# 3-H.net
KiCad netlist of a schematic drawn in Altium Designer
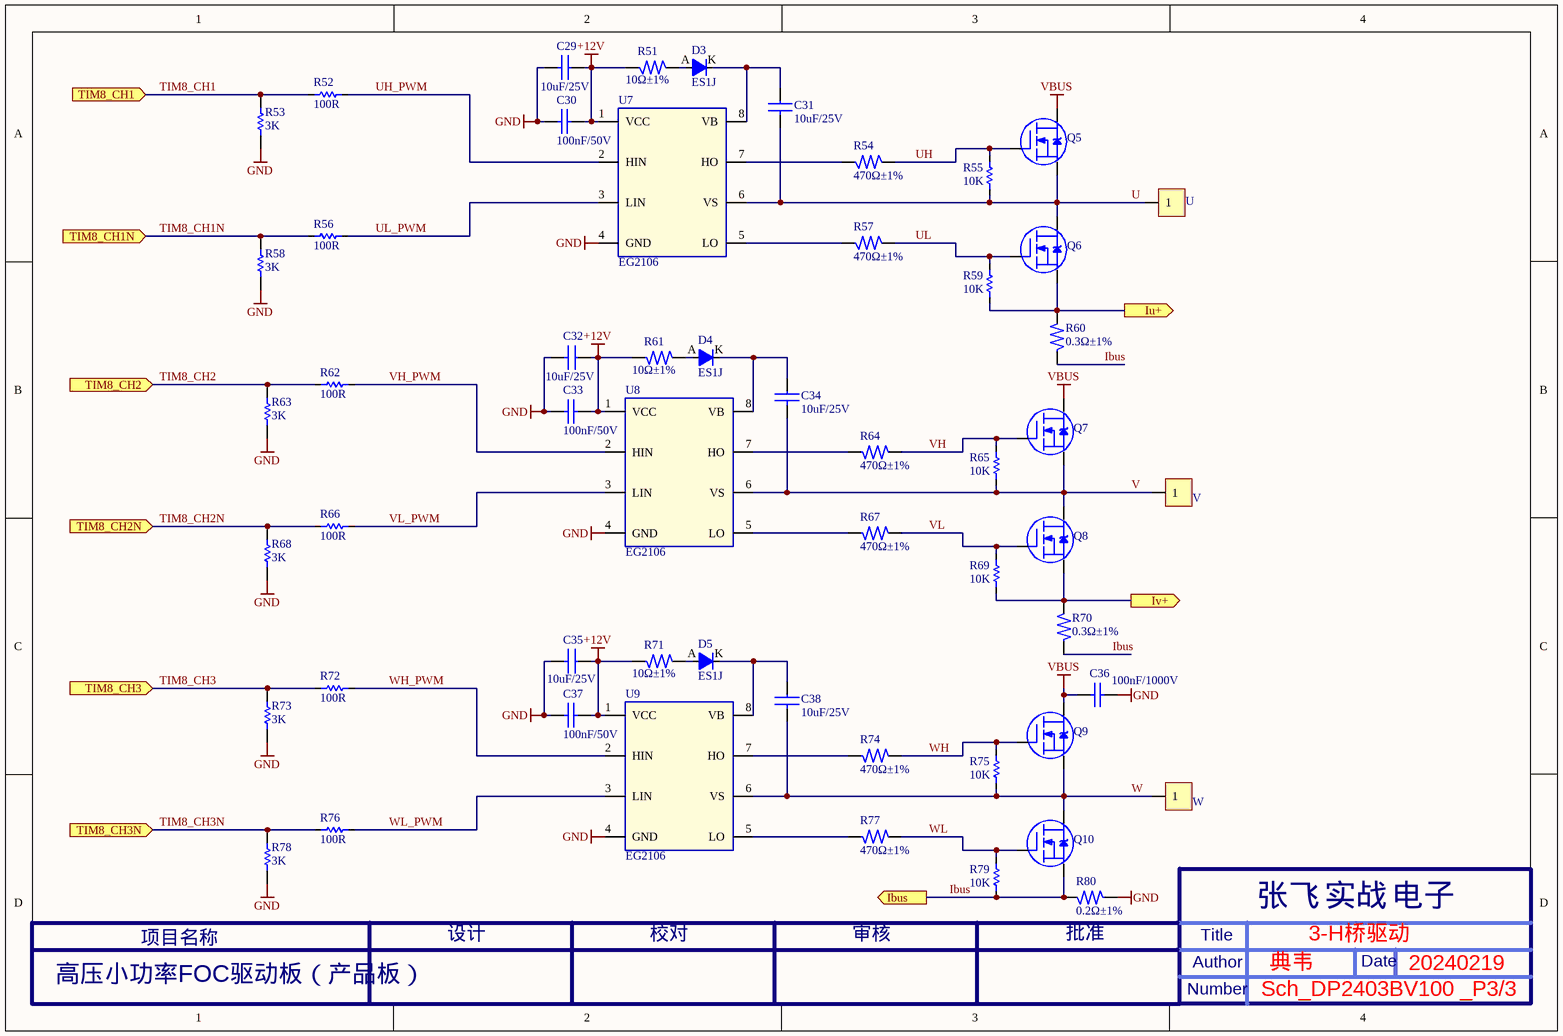
[diagram p0: 3-H桥驱动.SchDoc]

(export (version "E")
  (design (tool "Eeschema 10.0.6"))
  (components
    (comp (ref "C29")
      (value "10uF/25V")
      (footprint "C0805")
      (description "贴片电容")
      (fields
        (field (name "VOLTAGE") "<Voltage>")
        (field (name "MANUFACTURER") "TDK")
        (field (name "CREATED BY") "JJJ")
      )
      (libsource (lib "*") (part "CAP NP_0"))
    )
    (comp (ref "C30")
      (value "100nF/50V")
      (footprint "C0603")
      (description "贴片电容")
      (libsource (lib "*") (part "CAP"))
    )
    (comp (ref "C31")
      (value "10uF/25V")
      (footprint "C0805")
      (description "贴片电容")
      (fields
        (field (name "VOLTAGE") "<Voltage>")
        (field (name "MANUFACTURER") "TDK")
        (field (name "CREATED BY") "JJJ")
      )
      (libsource (lib "*") (part "CAP NP_0"))
    )
    (comp (ref "C32")
      (value "10uF/25V")
      (footprint "C0805")
      (description "贴片电容")
      (fields
        (field (name "VOLTAGE") "<Voltage>")
        (field (name "MANUFACTURER") "TDK")
        (field (name "CREATED BY") "JJJ")
      )
      (libsource (lib "*") (part "CAP NP_0"))
    )
    (comp (ref "C33")
      (value "100nF/50V")
      (footprint "C0603")
      (description "贴片电容")
      (libsource (lib "*") (part "CAP"))
    )
    (comp (ref "C34")
      (value "10uF/25V")
      (footprint "C0805")
      (description "贴片电容")
      (fields
        (field (name "VOLTAGE") "<Voltage>")
        (field (name "MANUFACTURER") "TDK")
        (field (name "CREATED BY") "JJJ")
      )
      (libsource (lib "*") (part "CAP NP_0"))
    )
    (comp (ref "C35")
      (value "10uF/25V")
      (footprint "C0805")
      (description "贴片电容")
      (fields
        (field (name "VOLTAGE") "<Voltage>")
        (field (name "MANUFACTURER") "TDK")
        (field (name "CREATED BY") "JJJ")
      )
      (libsource (lib "*") (part "CAP NP_0"))
    )
    (comp (ref "C36")
      (value "100nF/1000V")
      (footprint "C1812")
      (description "贴片电容")
      (libsource (lib "*") (part "CAP"))
    )
    (comp (ref "C37")
      (value "100nF/50V")
      (footprint "C0603")
      (description "贴片电容")
      (libsource (lib "*") (part "CAP"))
    )
    (comp (ref "C38")
      (value "10uF/25V")
      (footprint "C0805")
      (description "贴片电容")
      (fields
        (field (name "VOLTAGE") "<Voltage>")
        (field (name "MANUFACTURER") "TDK")
        (field (name "CREATED BY") "JJJ")
      )
      (libsource (lib "*") (part "CAP NP_0"))
    )
    (comp (ref "D3")
      (value "ES1J")
      (footprint "DO-214AC(SMA)")
      (description "二极管")
      (libsource (lib "ZF-V1.00(2022-6-13)") (part "DIO"))
    )
    (comp (ref "D4")
      (value "ES1J")
      (footprint "DO-214AC(SMA)")
      (description "二极管")
      (libsource (lib "ZF-V1.00(2022-6-13)") (part "DIO"))
    )
    (comp (ref "D5")
      (value "ES1J")
      (footprint "DO-214AC(SMA)")
      (description "二极管")
      (libsource (lib "ZF-V1.00(2022-6-13)") (part "DIO"))
    )
    (comp (ref "Q5")
      (value "MOT5N50D")
      (footprint "TO-252AA")
      (libsource (lib "吹风机-20231226") (part "MOT5N50D"))
    )
    (comp (ref "Q6")
      (value "MOT5N50D")
      (footprint "TO-252AA")
      (libsource (lib "吹风机-20231226") (part "MOT5N50D"))
    )
    (comp (ref "Q7")
      (value "MOT5N50D")
      (footprint "TO-252AA")
      (libsource (lib "吹风机-20231226") (part "MOT5N50D"))
    )
    (comp (ref "Q8")
      (value "MOT5N50D")
      (footprint "TO-252AA")
      (libsource (lib "吹风机-20231226") (part "MOT5N50D"))
    )
    (comp (ref "Q9")
      (value "MOT5N50D")
      (footprint "TO-252AA")
      (libsource (lib "吹风机-20231226") (part "MOT5N50D"))
    )
    (comp (ref "Q10")
      (value "MOT5N50D")
      (footprint "TO-252AA")
      (libsource (lib "吹风机-20231226") (part "MOT5N50D"))
    )
    (comp (ref "R51") (value "10Ω±1%") (footprint "R0805") (libsource (lib "EV") (part "RES")))
    (comp (ref "R52")
      (value "100R")
      (footprint "R0603")
      (description "电阻")
      (fields
        (field (name "MANUFACTURER") "Generic Components")
        (field (name "PUBLISHER") "Altium Hobart Technology Centre")
      )
      (libsource (lib "ZF-V1.00(2022-6-13)") (part "Res"))
    )
    (comp (ref "R53")
      (value "3K")
      (footprint "R0603")
      (description "电阻")
      (fields
        (field (name "MANUFACTURER") "Generic Components")
        (field (name "PUBLISHER") "Altium Hobart Technology Centre")
      )
      (libsource (lib "ZF_SchLib_V0.15") (part "Res"))
    )
    (comp (ref "R54") (value "470Ω±1%") (footprint "R0603") (libsource (lib "EV") (part "RES")))
    (comp (ref "R55")
      (value "10K")
      (footprint "R0603")
      (description "电阻")
      (fields
        (field (name "MANUFACTURER") "Generic Components")
        (field (name "PUBLISHER") "Altium Hobart Technology Centre")
      )
      (libsource (lib "ZF-V1.00(2022-6-13)") (part "Res"))
    )
    (comp (ref "R56")
      (value "100R")
      (footprint "R0603")
      (description "电阻")
      (fields
        (field (name "MANUFACTURER") "Generic Components")
        (field (name "PUBLISHER") "Altium Hobart Technology Centre")
      )
      (libsource (lib "ZF-V1.00(2022-6-13)") (part "Res"))
    )
    (comp (ref "R57") (value "470Ω±1%") (footprint "R0603") (libsource (lib "EV") (part "RES")))
    (comp (ref "R58")
      (value "3K")
      (footprint "R0603")
      (description "电阻")
      (fields
        (field (name "MANUFACTURER") "Generic Components")
        (field (name "PUBLISHER") "Altium Hobart Technology Centre")
      )
      (libsource (lib "ZF_SchLib_V0.15") (part "Res"))
    )
    (comp (ref "R59")
      (value "10K")
      (footprint "R0603")
      (description "电阻")
      (fields
        (field (name "MANUFACTURER") "Generic Components")
        (field (name "PUBLISHER") "Altium Hobart Technology Centre")
      )
      (libsource (lib "ZF-V1.00(2022-6-13)") (part "Res"))
    )
    (comp (ref "R60") (value "0.3Ω±1%") (footprint "R1206") (libsource (lib "EV") (part "RES")))
    (comp (ref "R61") (value "10Ω±1%") (footprint "R0805") (libsource (lib "EV") (part "RES")))
    (comp (ref "R62")
      (value "100R")
      (footprint "R0603")
      (description "电阻")
      (fields
        (field (name "MANUFACTURER") "Generic Components")
        (field (name "PUBLISHER") "Altium Hobart Technology Centre")
      )
      (libsource (lib "ZF-V1.00(2022-6-13)") (part "Res"))
    )
    (comp (ref "R63")
      (value "3K")
      (footprint "R0603")
      (description "电阻")
      (fields
        (field (name "MANUFACTURER") "Generic Components")
        (field (name "PUBLISHER") "Altium Hobart Technology Centre")
      )
      (libsource (lib "ZF_SchLib_V0.15") (part "Res"))
    )
    (comp (ref "R64") (value "470Ω±1%") (footprint "R0603") (libsource (lib "EV") (part "RES")))
    (comp (ref "R65")
      (value "10K")
      (footprint "R0603")
      (description "电阻")
      (fields
        (field (name "MANUFACTURER") "Generic Components")
        (field (name "PUBLISHER") "Altium Hobart Technology Centre")
      )
      (libsource (lib "ZF-V1.00(2022-6-13)") (part "Res"))
    )
    (comp (ref "R66")
      (value "100R")
      (footprint "R0603")
      (description "电阻")
      (fields
        (field (name "MANUFACTURER") "Generic Components")
        (field (name "PUBLISHER") "Altium Hobart Technology Centre")
      )
      (libsource (lib "ZF-V1.00(2022-6-13)") (part "Res"))
    )
    (comp (ref "R67") (value "470Ω±1%") (footprint "R0603") (libsource (lib "EV") (part "RES")))
    (comp (ref "R68")
      (value "3K")
      (footprint "R0603")
      (description "电阻")
      (fields
        (field (name "MANUFACTURER") "Generic Components")
        (field (name "PUBLISHER") "Altium Hobart Technology Centre")
      )
      (libsource (lib "ZF_SchLib_V0.15") (part "Res"))
    )
    (comp (ref "R69")
      (value "10K")
      (footprint "R0603")
      (description "电阻")
      (fields
        (field (name "MANUFACTURER") "Generic Components")
        (field (name "PUBLISHER") "Altium Hobart Technology Centre")
      )
      (libsource (lib "ZF-V1.00(2022-6-13)") (part "Res"))
    )
    (comp (ref "R70") (value "0.3Ω±1%") (footprint "R1206") (libsource (lib "EV") (part "RES")))
    (comp (ref "R71") (value "10Ω±1%") (footprint "R0805") (libsource (lib "EV") (part "RES")))
    (comp (ref "R72")
      (value "100R")
      (footprint "R0603")
      (description "电阻")
      (fields
        (field (name "MANUFACTURER") "Generic Components")
        (field (name "PUBLISHER") "Altium Hobart Technology Centre")
      )
      (libsource (lib "ZF-V1.00(2022-6-13)") (part "Res"))
    )
    (comp (ref "R73")
      (value "3K")
      (footprint "R0603")
      (description "电阻")
      (fields
        (field (name "MANUFACTURER") "Generic Components")
        (field (name "PUBLISHER") "Altium Hobart Technology Centre")
      )
      (libsource (lib "ZF_SchLib_V0.15") (part "Res"))
    )
    (comp (ref "R74") (value "470Ω±1%") (footprint "R0603") (libsource (lib "EV") (part "RES")))
    (comp (ref "R75")
      (value "10K")
      (footprint "R0603")
      (description "电阻")
      (fields
        (field (name "MANUFACTURER") "Generic Components")
        (field (name "PUBLISHER") "Altium Hobart Technology Centre")
      )
      (libsource (lib "ZF-V1.00(2022-6-13)") (part "Res"))
    )
    (comp (ref "R76")
      (value "100R")
      (footprint "R0603")
      (description "电阻")
      (fields
        (field (name "MANUFACTURER") "Generic Components")
        (field (name "PUBLISHER") "Altium Hobart Technology Centre")
      )
      (libsource (lib "ZF-V1.00(2022-6-13)") (part "Res"))
    )
    (comp (ref "R77") (value "470Ω±1%") (footprint "R0603") (libsource (lib "EV") (part "RES")))
    (comp (ref "R78")
      (value "3K")
      (footprint "R0603")
      (description "电阻")
      (fields
        (field (name "MANUFACTURER") "Generic Components")
        (field (name "PUBLISHER") "Altium Hobart Technology Centre")
      )
      (libsource (lib "ZF_SchLib_V0.15") (part "Res"))
    )
    (comp (ref "R79")
      (value "10K")
      (footprint "R0603")
      (description "电阻")
      (fields
        (field (name "MANUFACTURER") "Generic Components")
        (field (name "PUBLISHER") "Altium Hobart Technology Centre")
      )
      (libsource (lib "ZF-V1.00(2022-6-13)") (part "Res"))
    )
    (comp (ref "R80") (value "0.2Ω±1%") (footprint "R1206") (libsource (lib "EV") (part "RES")))
    (comp (ref "U")
      (value "U")
      (footprint "IGBT-PIN")
      (description "1Pin")
      (libsource (lib "ZF-V1.00(2022-6-13)") (part "Pin1"))
    )
    (comp (ref "U7") (value "EG2106") (footprint "SOIC-8") (libsource (lib "吹风机") (part "EG2106")))
    (comp (ref "U8") (value "EG2106") (footprint "SOIC-8") (libsource (lib "吹风机") (part "EG2106")))
    (comp (ref "U9") (value "EG2106") (footprint "SOIC-8") (libsource (lib "吹风机") (part "EG2106")))
    (comp (ref "V")
      (value "V")
      (footprint "IGBT-PIN")
      (description "1Pin")
      (libsource (lib "ZF-V1.00(2022-6-13)") (part "Pin1"))
    )
    (comp (ref "W")
      (value "W")
      (footprint "IGBT-PIN")
      (description "1Pin")
      (libsource (lib "ZF-V1.00(2022-6-13)") (part "Pin1"))
    )
  )
  (nets
    (net (code "1") (name "+12V") (class "Default")
      (node (ref "C29") (pin "1") (pinfunction "1_1") (pintype "passive"))
      (node (ref "C30") (pin "2") (pinfunction "2_2") (pintype "passive"))
      (node (ref "C32") (pin "1") (pinfunction "1_1") (pintype "passive"))
      (node (ref "C33") (pin "2") (pinfunction "2_2") (pintype "passive"))
      (node (ref "C35") (pin "1") (pinfunction "1_1") (pintype "passive"))
      (node (ref "C37") (pin "2") (pinfunction "2_2") (pintype "passive"))
      (node (ref "R51") (pin "1") (pintype "passive"))
      (node (ref "R61") (pin "1") (pintype "passive"))
      (node (ref "R71") (pin "1") (pintype "passive"))
      (node (ref "U7") (pin "1") (pinfunction "VCC_1") (pintype "passive"))
      (node (ref "U8") (pin "1") (pinfunction "VCC_1") (pintype "passive"))
      (node (ref "U9") (pin "1") (pinfunction "VCC_1") (pintype "passive"))
    )
    (net (code "2") (name "/Ibus") (class "Default")
      (node (ref "Q10") (pin "S") (pinfunction "S_S") (pintype "passive"))
      (node (ref "R60") (pin "1") (pintype "passive"))
      (node (ref "R70") (pin "1") (pintype "passive"))
      (node (ref "R79") (pin "2") (pinfunction "2_2") (pintype "passive"))
      (node (ref "R80") (pin "2") (pintype "passive"))
    )
    (net (code "3") (name "/Iu+") (class "Default")
      (node (ref "Q6") (pin "S") (pinfunction "S_S") (pintype "passive"))
      (node (ref "R59") (pin "2") (pinfunction "2_2") (pintype "passive"))
      (node (ref "R60") (pin "2") (pintype "passive"))
    )
    (net (code "4") (name "/Iv+") (class "Default")
      (node (ref "Q8") (pin "S") (pinfunction "S_S") (pintype "passive"))
      (node (ref "R69") (pin "2") (pinfunction "2_2") (pintype "passive"))
      (node (ref "R70") (pin "2") (pintype "passive"))
    )
    (net (code "5") (name "/TIM8_CH1") (class "Default")
      (node (ref "R52") (pin "1") (pinfunction "1_1") (pintype "passive"))
      (node (ref "R53") (pin "1") (pinfunction "1_1") (pintype "passive"))
    )
    (net (code "6") (name "/TIM8_CH1N") (class "Default")
      (node (ref "R56") (pin "1") (pinfunction "1_1") (pintype "passive"))
      (node (ref "R58") (pin "1") (pinfunction "1_1") (pintype "passive"))
    )
    (net (code "7") (name "/TIM8_CH2") (class "Default")
      (node (ref "R62") (pin "1") (pinfunction "1_1") (pintype "passive"))
      (node (ref "R63") (pin "1") (pinfunction "1_1") (pintype "passive"))
    )
    (net (code "8") (name "/TIM8_CH2N") (class "Default")
      (node (ref "R66") (pin "1") (pinfunction "1_1") (pintype "passive"))
      (node (ref "R68") (pin "1") (pinfunction "1_1") (pintype "passive"))
    )
    (net (code "9") (name "/TIM8_CH3") (class "Default")
      (node (ref "R72") (pin "1") (pinfunction "1_1") (pintype "passive"))
      (node (ref "R73") (pin "1") (pinfunction "1_1") (pintype "passive"))
    )
    (net (code "10") (name "/TIM8_CH3N") (class "Default")
      (node (ref "R76") (pin "1") (pinfunction "1_1") (pintype "passive"))
      (node (ref "R78") (pin "1") (pinfunction "1_1") (pintype "passive"))
    )
    (net (code "11") (name "/U") (class "Default")
      (node (ref "C31") (pin "2") (pinfunction "2_2") (pintype "passive"))
      (node (ref "Q5") (pin "S") (pinfunction "S_S") (pintype "passive"))
      (node (ref "Q6") (pin "D") (pinfunction "D_D") (pintype "passive"))
      (node (ref "R55") (pin "2") (pinfunction "2_2") (pintype "passive"))
      (node (ref "U") (pin "1") (pinfunction "1_1") (pintype "passive"))
      (node (ref "U7") (pin "6") (pinfunction "VS_6") (pintype "passive"))
    )
    (net (code "12") (name "/UH") (class "Default")
      (node (ref "Q5") (pin "G") (pinfunction "G_G") (pintype "passive"))
      (node (ref "R54") (pin "2") (pintype "passive"))
      (node (ref "R55") (pin "1") (pinfunction "1_1") (pintype "passive"))
    )
    (net (code "13") (name "/UH_PWM") (class "Default")
      (node (ref "R52") (pin "2") (pinfunction "2_2") (pintype "passive"))
      (node (ref "U7") (pin "2") (pinfunction "HIN_2") (pintype "passive"))
    )
    (net (code "14") (name "/UL") (class "Default")
      (node (ref "Q6") (pin "G") (pinfunction "G_G") (pintype "passive"))
      (node (ref "R57") (pin "2") (pintype "passive"))
      (node (ref "R59") (pin "1") (pinfunction "1_1") (pintype "passive"))
    )
    (net (code "15") (name "/UL_PWM") (class "Default")
      (node (ref "R56") (pin "2") (pinfunction "2_2") (pintype "passive"))
      (node (ref "U7") (pin "3") (pinfunction "LIN_3") (pintype "passive"))
    )
    (net (code "16") (name "/V") (class "Default")
      (node (ref "C34") (pin "2") (pinfunction "2_2") (pintype "passive"))
      (node (ref "Q7") (pin "S") (pinfunction "S_S") (pintype "passive"))
      (node (ref "Q8") (pin "D") (pinfunction "D_D") (pintype "passive"))
      (node (ref "R65") (pin "2") (pinfunction "2_2") (pintype "passive"))
      (node (ref "U8") (pin "6") (pinfunction "VS_6") (pintype "passive"))
      (node (ref "V") (pin "1") (pinfunction "1_1") (pintype "passive"))
    )
    (net (code "17") (name "/VH") (class "Default")
      (node (ref "Q7") (pin "G") (pinfunction "G_G") (pintype "passive"))
      (node (ref "R64") (pin "2") (pintype "passive"))
      (node (ref "R65") (pin "1") (pinfunction "1_1") (pintype "passive"))
    )
    (net (code "18") (name "/VH_PWM") (class "Default")
      (node (ref "R62") (pin "2") (pinfunction "2_2") (pintype "passive"))
      (node (ref "U8") (pin "2") (pinfunction "HIN_2") (pintype "passive"))
    )
    (net (code "19") (name "/VL") (class "Default")
      (node (ref "Q8") (pin "G") (pinfunction "G_G") (pintype "passive"))
      (node (ref "R67") (pin "2") (pintype "passive"))
      (node (ref "R69") (pin "1") (pinfunction "1_1") (pintype "passive"))
    )
    (net (code "20") (name "/VL_PWM") (class "Default")
      (node (ref "R66") (pin "2") (pinfunction "2_2") (pintype "passive"))
      (node (ref "U8") (pin "3") (pinfunction "LIN_3") (pintype "passive"))
    )
    (net (code "21") (name "/W") (class "Default")
      (node (ref "C38") (pin "2") (pinfunction "2_2") (pintype "passive"))
      (node (ref "Q10") (pin "D") (pinfunction "D_D") (pintype "passive"))
      (node (ref "Q9") (pin "S") (pinfunction "S_S") (pintype "passive"))
      (node (ref "R75") (pin "2") (pinfunction "2_2") (pintype "passive"))
      (node (ref "U9") (pin "6") (pinfunction "VS_6") (pintype "passive"))
      (node (ref "W") (pin "1") (pinfunction "1_1") (pintype "passive"))
    )
    (net (code "22") (name "/WH") (class "Default")
      (node (ref "Q9") (pin "G") (pinfunction "G_G") (pintype "passive"))
      (node (ref "R74") (pin "2") (pintype "passive"))
      (node (ref "R75") (pin "1") (pinfunction "1_1") (pintype "passive"))
    )
    (net (code "23") (name "/WH_PWM") (class "Default")
      (node (ref "R72") (pin "2") (pinfunction "2_2") (pintype "passive"))
      (node (ref "U9") (pin "2") (pinfunction "HIN_2") (pintype "passive"))
    )
    (net (code "24") (name "/WL") (class "Default")
      (node (ref "Q10") (pin "G") (pinfunction "G_G") (pintype "passive"))
      (node (ref "R77") (pin "2") (pintype "passive"))
      (node (ref "R79") (pin "1") (pinfunction "1_1") (pintype "passive"))
    )
    (net (code "25") (name "/WL_PWM") (class "Default")
      (node (ref "R76") (pin "2") (pinfunction "2_2") (pintype "passive"))
      (node (ref "U9") (pin "3") (pinfunction "LIN_3") (pintype "passive"))
    )
    (net (code "26") (name "GND") (class "Default")
      (node (ref "C29") (pin "2") (pinfunction "2_2") (pintype "passive"))
      (node (ref "C30") (pin "1") (pinfunction "1_1") (pintype "passive"))
      (node (ref "C32") (pin "2") (pinfunction "2_2") (pintype "passive"))
      (node (ref "C33") (pin "1") (pinfunction "1_1") (pintype "passive"))
      (node (ref "C35") (pin "2") (pinfunction "2_2") (pintype "passive"))
      (node (ref "C36") (pin "2") (pinfunction "2_2") (pintype "passive"))
      (node (ref "C37") (pin "1") (pinfunction "1_1") (pintype "passive"))
      (node (ref "R53") (pin "2") (pinfunction "2_2") (pintype "passive"))
      (node (ref "R58") (pin "2") (pinfunction "2_2") (pintype "passive"))
      (node (ref "R63") (pin "2") (pinfunction "2_2") (pintype "passive"))
      (node (ref "R68") (pin "2") (pinfunction "2_2") (pintype "passive"))
      (node (ref "R73") (pin "2") (pinfunction "2_2") (pintype "passive"))
      (node (ref "R78") (pin "2") (pinfunction "2_2") (pintype "passive"))
      (node (ref "R80") (pin "1") (pintype "passive"))
      (node (ref "U7") (pin "4") (pinfunction "GND_4") (pintype "passive"))
      (node (ref "U8") (pin "4") (pinfunction "GND_4") (pintype "passive"))
      (node (ref "U9") (pin "4") (pinfunction "GND_4") (pintype "passive"))
    )
    (net (code "27") (name "Net-(D3-PadA)") (class "Default")
      (node (ref "D3") (pin "A") (pinfunction "A_A") (pintype "passive"))
      (node (ref "R51") (pin "2") (pintype "passive"))
    )
    (net (code "28") (name "Net-(D4-PadA)") (class "Default")
      (node (ref "D4") (pin "A") (pinfunction "A_A") (pintype "passive"))
      (node (ref "R61") (pin "2") (pintype "passive"))
    )
    (net (code "29") (name "Net-(D5-PadA)") (class "Default")
      (node (ref "D5") (pin "A") (pinfunction "A_A") (pintype "passive"))
      (node (ref "R71") (pin "2") (pintype "passive"))
    )
    (net (code "30") (name "Net-(U7-HO)") (class "Default")
      (node (ref "R54") (pin "1") (pintype "passive"))
      (node (ref "U7") (pin "7") (pinfunction "HO_7") (pintype "passive"))
    )
    (net (code "31") (name "Net-(U7-LO)") (class "Default")
      (node (ref "R57") (pin "1") (pintype "passive"))
      (node (ref "U7") (pin "5") (pinfunction "LO_5") (pintype "passive"))
    )
    (net (code "32") (name "Net-(U7-VB)") (class "Default")
      (node (ref "C31") (pin "1") (pinfunction "1_1") (pintype "passive"))
      (node (ref "D3") (pin "K") (pinfunction "K_K") (pintype "passive"))
      (node (ref "U7") (pin "8") (pinfunction "VB_8") (pintype "passive"))
    )
    (net (code "33") (name "Net-(U8-HO)") (class "Default")
      (node (ref "R64") (pin "1") (pintype "passive"))
      (node (ref "U8") (pin "7") (pinfunction "HO_7") (pintype "passive"))
    )
    (net (code "34") (name "Net-(U8-LO)") (class "Default")
      (node (ref "R67") (pin "1") (pintype "passive"))
      (node (ref "U8") (pin "5") (pinfunction "LO_5") (pintype "passive"))
    )
    (net (code "35") (name "Net-(U8-VB)") (class "Default")
      (node (ref "C34") (pin "1") (pinfunction "1_1") (pintype "passive"))
      (node (ref "D4") (pin "K") (pinfunction "K_K") (pintype "passive"))
      (node (ref "U8") (pin "8") (pinfunction "VB_8") (pintype "passive"))
    )
    (net (code "36") (name "Net-(U9-HO)") (class "Default")
      (node (ref "R74") (pin "1") (pintype "passive"))
      (node (ref "U9") (pin "7") (pinfunction "HO_7") (pintype "passive"))
    )
    (net (code "37") (name "Net-(U9-LO)") (class "Default")
      (node (ref "R77") (pin "1") (pintype "passive"))
      (node (ref "U9") (pin "5") (pinfunction "LO_5") (pintype "passive"))
    )
    (net (code "38") (name "Net-(U9-VB)") (class "Default")
      (node (ref "C38") (pin "1") (pinfunction "1_1") (pintype "passive"))
      (node (ref "D5") (pin "K") (pinfunction "K_K") (pintype "passive"))
      (node (ref "U9") (pin "8") (pinfunction "VB_8") (pintype "passive"))
    )
    (net (code "39") (name "VBUS") (class "Default")
      (node (ref "C36") (pin "1") (pinfunction "1_1") (pintype "passive"))
      (node (ref "Q5") (pin "D") (pinfunction "D_D") (pintype "passive"))
      (node (ref "Q7") (pin "D") (pinfunction "D_D") (pintype "passive"))
      (node (ref "Q9") (pin "D") (pinfunction "D_D") (pintype "passive"))
    )
  )
)
